# PLL.net
KiCad netlist of a schematic drawn in Altium Designer
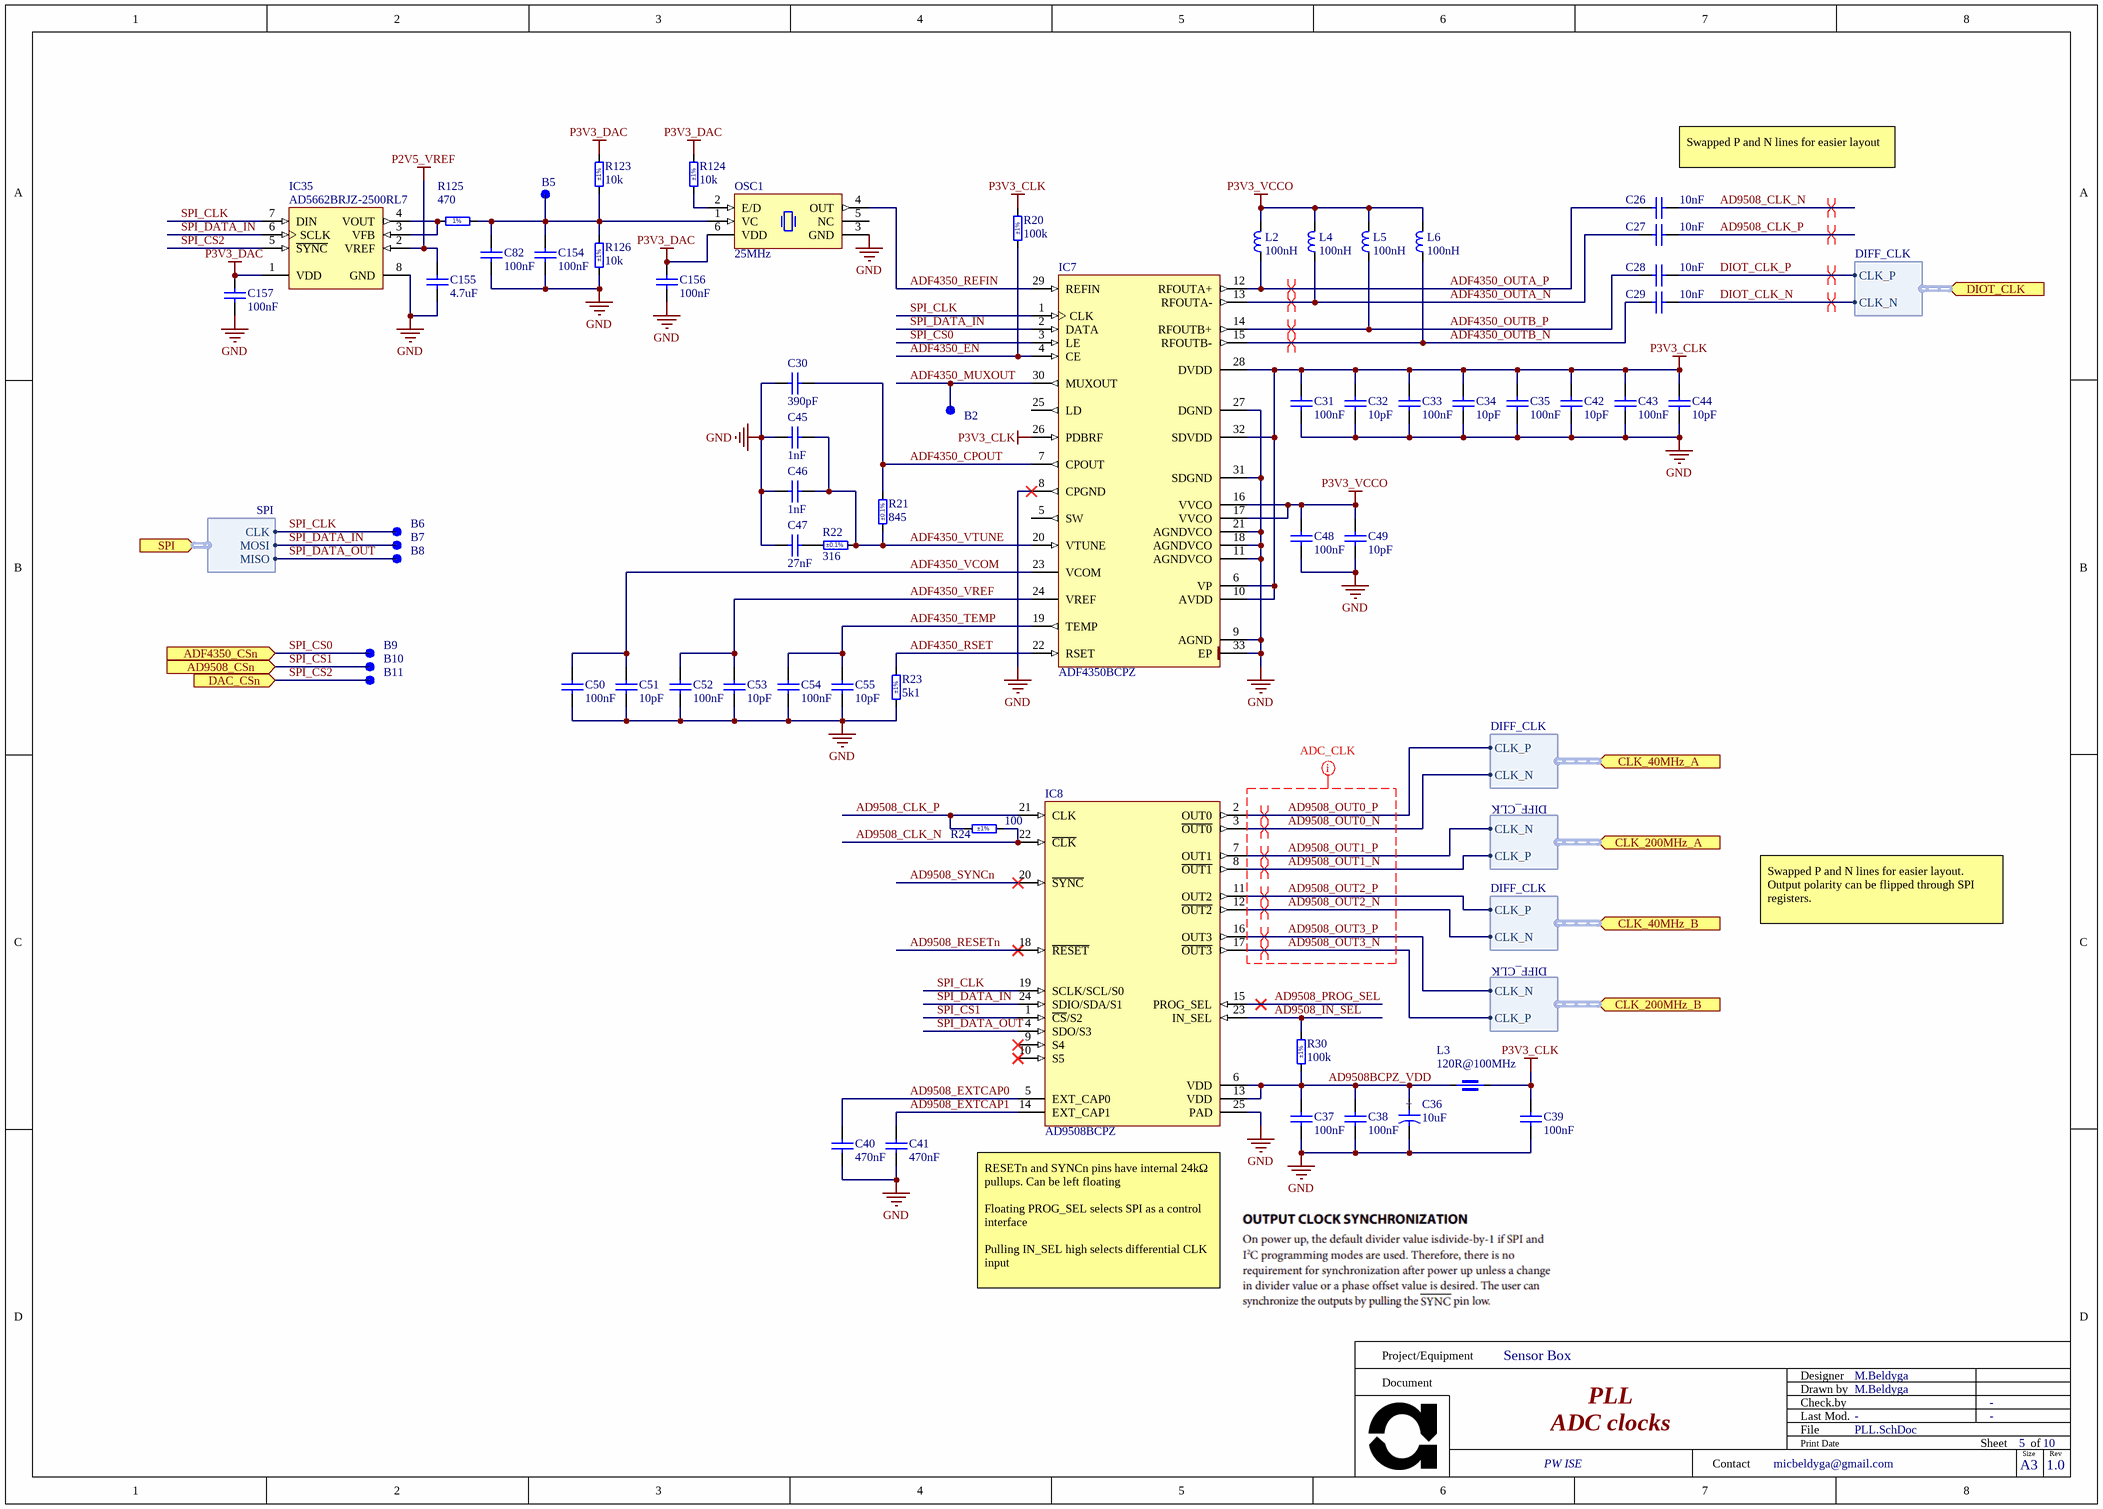
[diagram p0: PLL.SchDoc]

(export (version "E")
  (design (tool "Eeschema 10.0.6"))
  (components
    (comp (ref "B2")
      (value "SMD Pad")
      (footprint "C100")
      (description "Pad")
      (fields (field (name "PART NUMBER") "SMD_PAD_D1MM") (field (name "AUTHOR") "CERN DEM JLC"))
      (libsource (lib "Eletro-mechanical") (part "Single SMD Pad (Round)"))
    )
    (comp (ref "B5")
      (value "SMD Pad")
      (footprint "C100")
      (description "Pad")
      (fields (field (name "PART NUMBER") "SMD_PAD_D1MM") (field (name "AUTHOR") "CERN DEM JLC"))
      (libsource (lib "Eletro-mechanical") (part "Single SMD Pad (Round)"))
    )
    (comp (ref "B6")
      (value "SMD Pad")
      (footprint "C100")
      (description "Pad")
      (fields (field (name "PART NUMBER") "SMD_PAD_D1MM") (field (name "AUTHOR") "CERN DEM JLC"))
      (libsource (lib "Eletro-mechanical") (part "Single SMD Pad (Round)"))
    )
    (comp (ref "B7")
      (value "SMD Pad")
      (footprint "C100")
      (description "Pad")
      (fields (field (name "PART NUMBER") "SMD_PAD_D1MM") (field (name "AUTHOR") "CERN DEM JLC"))
      (libsource (lib "Eletro-mechanical") (part "Single SMD Pad (Round)"))
    )
    (comp (ref "B8")
      (value "SMD Pad")
      (footprint "C100")
      (description "Pad")
      (fields (field (name "PART NUMBER") "SMD_PAD_D1MM") (field (name "AUTHOR") "CERN DEM JLC"))
      (libsource (lib "Eletro-mechanical") (part "Single SMD Pad (Round)"))
    )
    (comp (ref "B9")
      (value "SMD Pad")
      (footprint "C100")
      (description "Pad")
      (fields (field (name "PART NUMBER") "SMD_PAD_D1MM") (field (name "AUTHOR") "CERN DEM JLC"))
      (libsource (lib "Eletro-mechanical") (part "Single SMD Pad (Round)"))
    )
    (comp (ref "B10")
      (value "SMD Pad")
      (footprint "C100")
      (description "Pad")
      (fields (field (name "PART NUMBER") "SMD_PAD_D1MM") (field (name "AUTHOR") "CERN DEM JLC"))
      (libsource (lib "Eletro-mechanical") (part "Single SMD Pad (Round)"))
    )
    (comp (ref "B11")
      (value "SMD Pad")
      (footprint "C100")
      (description "Pad")
      (fields (field (name "PART NUMBER") "SMD_PAD_D1MM") (field (name "AUTHOR") "CERN DEM JLC"))
      (libsource (lib "Eletro-mechanical") (part "Single SMD Pad (Round)"))
    )
    (comp (ref "C26")
      (value "10nF")
      (footprint "CAPC1005X55N")
      (description "Non-polarised capacitor")
      (fields
        (field (name "PART NUMBER") "CC0402_10NF_16V_10%_X7R")
        (field (name "VOLTAGE") "16V")
        (field (name "AUTHOR") "CERN DEM JLC")
      )
      (libsource (lib "Capacitors") (part "Capacitor - non polarized"))
    )
    (comp (ref "C27")
      (value "10nF")
      (footprint "CAPC1005X55N")
      (description "Non-polarised capacitor")
      (fields
        (field (name "PART NUMBER") "CC0402_10NF_16V_10%_X7R")
        (field (name "VOLTAGE") "16V")
        (field (name "AUTHOR") "CERN DEM JLC")
      )
      (libsource (lib "Capacitors") (part "Capacitor - non polarized"))
    )
    (comp (ref "C28")
      (value "10nF")
      (footprint "CAPC1005X55N")
      (description "Non-polarised capacitor")
      (fields
        (field (name "PART NUMBER") "CC0402_10NF_16V_10%_X7R")
        (field (name "VOLTAGE") "16V")
        (field (name "AUTHOR") "CERN DEM JLC")
      )
      (libsource (lib "Capacitors") (part "Capacitor - non polarized"))
    )
    (comp (ref "C29")
      (value "10nF")
      (footprint "CAPC1005X55N")
      (description "Non-polarised capacitor")
      (fields
        (field (name "PART NUMBER") "CC0402_10NF_16V_10%_X7R")
        (field (name "VOLTAGE") "16V")
        (field (name "AUTHOR") "CERN DEM JLC")
      )
      (libsource (lib "Capacitors") (part "Capacitor - non polarized"))
    )
    (comp (ref "C30")
      (value "390pF")
      (footprint "CAPC1005X55N")
      (description "Non-polarised capacitor")
      (fields
        (field (name "PART NUMBER") "CC0402_390PF_50V_1%_C0G_MURATA_GCM1555C1H391FA16")
        (field (name "VOLTAGE") "50V")
        (field (name "AUTHOR") "CERN DEM BC")
      )
      (libsource (lib "Capacitors") (part "Capacitor - non polarized"))
    )
    (comp (ref "C31")
      (value "100nF")
      (footprint "CAPC1005X55N")
      (description "Non-polarised capacitor")
      (fields
        (field (name "PART NUMBER") "CC0402_100NF_50V_10%_X7R")
        (field (name "VOLTAGE") "50V")
        (field (name "AUTHOR") "CERN DEM MR")
      )
      (libsource (lib "Capacitors") (part "Capacitor - non polarized"))
    )
    (comp (ref "C32")
      (value "10pF")
      (footprint "CAPC1005X55N")
      (description "Non-polarised capacitor")
      (fields
        (field (name "PART NUMBER") "CC0402_10PF_50V_5%_C0G")
        (field (name "VOLTAGE") "50V")
        (field (name "AUTHOR") "CERN DEM JLC")
      )
      (libsource (lib "Capacitors") (part "Capacitor - non polarized"))
    )
    (comp (ref "C33")
      (value "100nF")
      (footprint "CAPC1005X55N")
      (description "Non-polarised capacitor")
      (fields
        (field (name "PART NUMBER") "CC0402_100NF_50V_10%_X7R")
        (field (name "VOLTAGE") "50V")
        (field (name "AUTHOR") "CERN DEM MR")
      )
      (libsource (lib "Capacitors") (part "Capacitor - non polarized"))
    )
    (comp (ref "C34")
      (value "10pF")
      (footprint "CAPC1005X55N")
      (description "Non-polarised capacitor")
      (fields
        (field (name "PART NUMBER") "CC0402_10PF_50V_5%_C0G")
        (field (name "VOLTAGE") "50V")
        (field (name "AUTHOR") "CERN DEM JLC")
      )
      (libsource (lib "Capacitors") (part "Capacitor - non polarized"))
    )
    (comp (ref "C35")
      (value "100nF")
      (footprint "CAPC1005X55N")
      (description "Non-polarised capacitor")
      (fields
        (field (name "PART NUMBER") "CC0402_100NF_50V_10%_X7R")
        (field (name "VOLTAGE") "50V")
        (field (name "AUTHOR") "CERN DEM MR")
      )
      (libsource (lib "Capacitors") (part "Capacitor - non polarized"))
    )
    (comp (ref "C36")
      (value "10uF")
      (footprint "CAPMP3216X180N")
      (description "Polarised capacitor")
      (fields
        (field (name "PART NUMBER") "CTE3216-18_10UF_16V_20%_AVX_TCJ")
        (field (name "VOLTAGE") "16V")
        (field (name "AUTHOR") "CERN DEM JLC")
      )
      (libsource (lib "Capacitors") (part "Capacitor - polarized"))
    )
    (comp (ref "C37")
      (value "100nF")
      (footprint "CAPC1005X55N")
      (description "Non-polarised capacitor")
      (fields
        (field (name "PART NUMBER") "CC0402_100NF_50V_10%_X7R")
        (field (name "VOLTAGE") "50V")
        (field (name "AUTHOR") "CERN DEM MR")
      )
      (libsource (lib "Capacitors") (part "Capacitor - non polarized"))
    )
    (comp (ref "C38")
      (value "100nF")
      (footprint "CAPC1005X55N")
      (description "Non-polarised capacitor")
      (fields
        (field (name "PART NUMBER") "CC0402_100NF_50V_10%_X7R")
        (field (name "VOLTAGE") "50V")
        (field (name "AUTHOR") "CERN DEM MR")
      )
      (libsource (lib "Capacitors") (part "Capacitor - non polarized"))
    )
    (comp (ref "C39")
      (value "100nF")
      (footprint "CAPC1005X55N")
      (description "Non-polarised capacitor")
      (fields
        (field (name "PART NUMBER") "CC0402_100NF_50V_10%_X7R")
        (field (name "VOLTAGE") "50V")
        (field (name "AUTHOR") "CERN DEM MR")
      )
      (libsource (lib "Capacitors") (part "Capacitor - non polarized"))
    )
    (comp (ref "C40")
      (value "470nF")
      (footprint "CAPC1005X55N")
      (description "Non-polarised capacitor")
      (fields
        (field (name "PART NUMBER") "CC0402_470NF_16V_10%_X5R")
        (field (name "VOLTAGE") "16V")
        (field (name "AUTHOR") "CERN DEM JLC")
      )
      (libsource (lib "Capacitors") (part "Capacitor - non polarized"))
    )
    (comp (ref "C41")
      (value "470nF")
      (footprint "CAPC1005X55N")
      (description "Non-polarised capacitor")
      (fields
        (field (name "PART NUMBER") "CC0402_470NF_16V_10%_X5R")
        (field (name "VOLTAGE") "16V")
        (field (name "AUTHOR") "CERN DEM JLC")
      )
      (libsource (lib "Capacitors") (part "Capacitor - non polarized"))
    )
    (comp (ref "C42")
      (value "10pF")
      (footprint "CAPC1005X55N")
      (description "Non-polarised capacitor")
      (fields
        (field (name "PART NUMBER") "CC0402_10PF_50V_5%_C0G")
        (field (name "VOLTAGE") "50V")
        (field (name "AUTHOR") "CERN DEM JLC")
      )
      (libsource (lib "Capacitors") (part "Capacitor - non polarized"))
    )
    (comp (ref "C43")
      (value "100nF")
      (footprint "CAPC1005X55N")
      (description "Non-polarised capacitor")
      (fields
        (field (name "PART NUMBER") "CC0402_100NF_50V_10%_X7R")
        (field (name "VOLTAGE") "50V")
        (field (name "AUTHOR") "CERN DEM MR")
      )
      (libsource (lib "Capacitors") (part "Capacitor - non polarized"))
    )
    (comp (ref "C44")
      (value "10pF")
      (footprint "CAPC1005X55N")
      (description "Non-polarised capacitor")
      (fields
        (field (name "PART NUMBER") "CC0402_10PF_50V_5%_C0G")
        (field (name "VOLTAGE") "50V")
        (field (name "AUTHOR") "CERN DEM JLC")
      )
      (libsource (lib "Capacitors") (part "Capacitor - non polarized"))
    )
    (comp (ref "C45")
      (value "1nF")
      (footprint "CAPC1608X90N")
      (description "Non-polarised capacitor")
      (fields
        (field (name "PART NUMBER") "CC0603_1NF_50V_1%_NP0")
        (field (name "VOLTAGE") "50V")
        (field (name "AUTHOR") "CERN DEM JLC")
      )
      (libsource (lib "Capacitors") (part "Capacitor - non polarized"))
    )
    (comp (ref "C46")
      (value "1nF")
      (footprint "CAPC1608X90N")
      (description "Non-polarised capacitor")
      (fields
        (field (name "PART NUMBER") "CC0603_1NF_50V_1%_NP0")
        (field (name "VOLTAGE") "50V")
        (field (name "AUTHOR") "CERN DEM JLC")
      )
      (libsource (lib "Capacitors") (part "Capacitor - non polarized"))
    )
    (comp (ref "C47")
      (value "27nF")
      (footprint "CAPC1005X55N")
      (description "Non-polarised capacitor")
      (fields
        (field (name "PART NUMBER") "CC0402_27NF_25V_10%_X7R")
        (field (name "VOLTAGE") "25V")
        (field (name "AUTHOR") "CERN DEM JLC")
      )
      (libsource (lib "Capacitors") (part "Capacitor - non polarized"))
    )
    (comp (ref "C48")
      (value "100nF")
      (footprint "CAPC1005X55N")
      (description "Non-polarised capacitor")
      (fields
        (field (name "PART NUMBER") "CC0402_100NF_50V_10%_X7R")
        (field (name "VOLTAGE") "50V")
        (field (name "AUTHOR") "CERN DEM MR")
      )
      (libsource (lib "Capacitors") (part "Capacitor - non polarized"))
    )
    (comp (ref "C49")
      (value "10pF")
      (footprint "CAPC1005X55N")
      (description "Non-polarised capacitor")
      (fields
        (field (name "PART NUMBER") "CC0402_10PF_50V_5%_C0G")
        (field (name "VOLTAGE") "50V")
        (field (name "AUTHOR") "CERN DEM JLC")
      )
      (libsource (lib "Capacitors") (part "Capacitor - non polarized"))
    )
    (comp (ref "C50")
      (value "100nF")
      (footprint "CAPC1005X55N")
      (description "Non-polarised capacitor")
      (fields
        (field (name "PART NUMBER") "CC0402_100NF_50V_10%_X7R")
        (field (name "VOLTAGE") "50V")
        (field (name "AUTHOR") "CERN DEM MR")
      )
      (libsource (lib "Capacitors") (part "Capacitor - non polarized"))
    )
    (comp (ref "C51")
      (value "10pF")
      (footprint "CAPC1005X55N")
      (description "Non-polarised capacitor")
      (fields
        (field (name "PART NUMBER") "CC0402_10PF_50V_5%_C0G")
        (field (name "VOLTAGE") "50V")
        (field (name "AUTHOR") "CERN DEM JLC")
      )
      (libsource (lib "Capacitors") (part "Capacitor - non polarized"))
    )
    (comp (ref "C52")
      (value "100nF")
      (footprint "CAPC1005X55N")
      (description "Non-polarised capacitor")
      (fields
        (field (name "PART NUMBER") "CC0402_100NF_50V_10%_X7R")
        (field (name "VOLTAGE") "50V")
        (field (name "AUTHOR") "CERN DEM MR")
      )
      (libsource (lib "Capacitors") (part "Capacitor - non polarized"))
    )
    (comp (ref "C53")
      (value "10pF")
      (footprint "CAPC1005X55N")
      (description "Non-polarised capacitor")
      (fields
        (field (name "PART NUMBER") "CC0402_10PF_50V_5%_C0G")
        (field (name "VOLTAGE") "50V")
        (field (name "AUTHOR") "CERN DEM JLC")
      )
      (libsource (lib "Capacitors") (part "Capacitor - non polarized"))
    )
    (comp (ref "C54")
      (value "100nF")
      (footprint "CAPC1005X55N")
      (description "Non-polarised capacitor")
      (fields
        (field (name "PART NUMBER") "CC0402_100NF_50V_10%_X7R")
        (field (name "VOLTAGE") "50V")
        (field (name "AUTHOR") "CERN DEM MR")
      )
      (libsource (lib "Capacitors") (part "Capacitor - non polarized"))
    )
    (comp (ref "C55")
      (value "10pF")
      (footprint "CAPC1005X55N")
      (description "Non-polarised capacitor")
      (fields
        (field (name "PART NUMBER") "CC0402_10PF_50V_5%_C0G")
        (field (name "VOLTAGE") "50V")
        (field (name "AUTHOR") "CERN DEM JLC")
      )
      (libsource (lib "Capacitors") (part "Capacitor - non polarized"))
    )
    (comp (ref "C82")
      (value "100nF")
      (footprint "CAPC1005X55N")
      (description "Non-polarised capacitor")
      (fields
        (field (name "PART NUMBER") "CC0402_100NF_50V_10%_X7R")
        (field (name "VOLTAGE") "50V")
        (field (name "AUTHOR") "CERN DEM MR")
      )
      (libsource (lib "Capacitors") (part "Capacitor - non polarized"))
    )
    (comp (ref "C154")
      (value "100nF")
      (footprint "CAPC1005X55N")
      (description "Non-polarised capacitor")
      (fields
        (field (name "PART NUMBER") "CC0402_100NF_50V_10%_X7R")
        (field (name "VOLTAGE") "50V")
        (field (name "AUTHOR") "CERN DEM MR")
      )
      (libsource (lib "Capacitors") (part "Capacitor - non polarized"))
    )
    (comp (ref "C155")
      (value "4.7uF")
      (footprint "CAPC1608X90N")
      (description "Non-polarised capacitor")
      (fields
        (field (name "PART NUMBER") "CC0603_4.7UF_25V_10%_X5R")
        (field (name "VOLTAGE") "25V")
        (field (name "AUTHOR") "CERN DEM JLC")
      )
      (libsource (lib "Capacitors") (part "Capacitor - non polarized"))
    )
    (comp (ref "C156")
      (value "100nF")
      (footprint "CAPC1005X55N")
      (description "Non-polarised capacitor")
      (fields
        (field (name "PART NUMBER") "CC0402_100NF_50V_10%_X7R")
        (field (name "VOLTAGE") "50V")
        (field (name "AUTHOR") "CERN DEM MR")
      )
      (libsource (lib "Capacitors") (part "Capacitor - non polarized"))
    )
    (comp (ref "C157")
      (value "100nF")
      (footprint "CAPC1005X55N")
      (description "Non-polarised capacitor")
      (fields
        (field (name "PART NUMBER") "CC0402_100NF_50V_10%_X7R")
        (field (name "VOLTAGE") "50V")
        (field (name "AUTHOR") "CERN DEM MR")
      )
      (libsource (lib "Capacitors") (part "Capacitor - non polarized"))
    )
    (comp (ref "IC7")
      (value "ADF4350BCPZ")
      (footprint "QFN50P500X500X80-33N-S325")
      (description "Wideband Synthesizer with Integrated VCO")
      (fields
        (field (name "MANUFACTURER") "Analog Devices")
        (field (name "MANUFACTURER PART NUMBER") "ADF4351BCP")
        (field (name "AUTHOR") "Michal Beldyga")
      )
      (libsource (lib "Semiconductors") (part "ADF4350"))
    )
    (comp (ref "IC8")
      (value "AD9508BCPZ")
      (footprint "QFN50P400X400X80_HS-25N")
      (description "1.65 GHz Clock Fanout Buffer with Output Dividers and Delay Adjust")
      (fields (field (name "MANUFACTURER") "Analog Devices") (field (name "AUTHOR") "Michal Beldyga"))
      (libsource (lib "Semiconductors") (part "AD9508"))
    )
    (comp (ref "IC35")
      (value "AD5662BRJZ-2500RL7")
      (footprint "SOT65P280X145-8N")
      (description "2.7V to 5.5V, 250µA, Rail-to-Rail Output 16-Bit nanoDAC")
      (fields
        (field (name "MANUFACTURER") "ANALOG DEVICES")
        (field (name "MANUFACTURER PART NUMBER") "AD5662BRJZ-2")
        (field (name "AUTHOR") "CERN DEM JLC")
      )
      (libsource (lib "ICs And Semiconductors") (part "AD5662"))
    )
    (comp (ref "L2")
      (value "100nH")
      (footprint "INDC1005X55N")
      (description "Inductor")
      (fields
        (field (name "PART NUMBER") "IND0402_100NH_5%_JOHANSON_ L-07CR10JV6T")
        (field (name "TOLERANCE") "±5%")
        (field (name "AUTHOR") "Michal Beldyga")
      )
      (libsource (lib "Inductors Transformers") (part "Inductor"))
    )
    (comp (ref "L3")
      (value "120R@100MHz")
      (footprint "INDC1608X65N")
      (fields
        (field (name "PART NUMBER") "IND0603_MURATA_BLM18SG121TN1D")
        (field (name "POWER") "3A")
        (field (name "TOLERANCE") "±25%")
        (field (name "AUTHOR") "CERN DEM JLC")
      )
      (libsource (lib "Inductors & Transformers") (part "Ferrite Bead"))
    )
    (comp (ref "L4")
      (value "100nH")
      (footprint "INDC1005X55N")
      (description "Inductor")
      (fields
        (field (name "PART NUMBER") "IND0402_100NH_5%_JOHANSON_ L-07CR10JV6T")
        (field (name "TOLERANCE") "±5%")
        (field (name "AUTHOR") "Michal Beldyga")
      )
      (libsource (lib "Inductors Transformers") (part "Inductor"))
    )
    (comp (ref "L5")
      (value "100nH")
      (footprint "INDC1005X55N")
      (description "Inductor")
      (fields
        (field (name "PART NUMBER") "IND0402_100NH_5%_JOHANSON_ L-07CR10JV6T")
        (field (name "TOLERANCE") "±5%")
        (field (name "AUTHOR") "Michal Beldyga")
      )
      (libsource (lib "Inductors Transformers") (part "Inductor"))
    )
    (comp (ref "L6")
      (value "100nH")
      (footprint "INDC1005X55N")
      (description "Inductor")
      (fields
        (field (name "PART NUMBER") "IND0402_100NH_5%_JOHANSON_ L-07CR10JV6T")
        (field (name "TOLERANCE") "±5%")
        (field (name "AUTHOR") "Michal Beldyga")
      )
      (libsource (lib "Inductors Transformers") (part "Inductor"))
    )
    (comp (ref "OSC1")
      (value "25MHz")
      (footprint "OSC_PERICOM_FRETHE025")
      (description "3.3V CMOS 25.000MHz Ethernet VCXO")
      (fields
        (field (name "PART NUMBER") "OSC_25MHZ_PERICOM_FRETHE025")
        (field (name "MANUFACTURER") "PERICOM")
        (field (name "AUTHOR") "CERN DEM JLC")
      )
      (libsource (lib "ICs And Semiconductors") (part "Oscillator PERICOM_FRETHE025"))
    )
    (comp (ref "R20")
      (value "100k")
      (footprint "RESC1005X40N")
      (description "Resistor - 1%")
      (fields
        (field (name "TOLERANCE") "±1%")
        (field (name "PART NUMBER") "R0402_100K_1%_0.0625W_100PPM")
        (field (name "POWER") "0.0625W")
        (field (name "AUTHOR") "CERN DEM JLC")
      )
      (libsource (lib "Resistors") (part "Resistor - 1%"))
    )
    (comp (ref "R21")
      (value "845")
      (footprint "RESC1608X55N")
      (description "Resistor - 0.1%")
      (fields
        (field (name "TOLERANCE") "±0.1%")
        (field (name "PART NUMBER") "R0603_845R_0.1%_0.063W_10PPM")
        (field (name "POWER") "0.063W")
        (field (name "AUTHOR") "CERN DEM JLC")
      )
      (libsource (lib "Resistors") (part "Resistor - 0.1%"))
    )
    (comp (ref "R22")
      (value "316")
      (footprint "RESC1608X55N")
      (description "Resistor - 0.1%")
      (fields
        (field (name "TOLERANCE") "±0.1%")
        (field (name "PART NUMBER") "R0603_316R_0.1%_0.063W_10PPM")
        (field (name "POWER") "0.063W")
        (field (name "AUTHOR") "CERN DEM JLC")
      )
      (libsource (lib "Resistors") (part "Resistor - 0.1%"))
    )
    (comp (ref "R23")
      (value "5k1")
      (footprint "RESC1005X40N")
      (description "Resistor - 1%")
      (fields
        (field (name "TOLERANCE") "±1%")
        (field (name "PART NUMBER") "R0402_5K1_1%_0.0625W_100PPM")
        (field (name "POWER") "0.0625W")
        (field (name "AUTHOR") "CERN DEM JLC")
      )
      (libsource (lib "Resistors") (part "Resistor - 1%"))
    )
    (comp (ref "R24")
      (value "100")
      (footprint "RESC1005X40N")
      (description "Resistor - 1%")
      (fields
        (field (name "TOLERANCE") "±1%")
        (field (name "PART NUMBER") "R0402_100R_1%_0.1W_100PPM")
        (field (name "POWER") "0.1W")
        (field (name "AUTHOR") "CERN DEM JLC")
      )
      (libsource (lib "Resistors") (part "Resistor - 1%"))
    )
    (comp (ref "R30")
      (value "100k")
      (footprint "RESC1005X40N")
      (description "Resistor - 1%")
      (fields
        (field (name "TOLERANCE") "±1%")
        (field (name "PART NUMBER") "R0402_100K_1%_0.0625W_100PPM")
        (field (name "POWER") "0.0625W")
        (field (name "AUTHOR") "CERN DEM JLC")
      )
      (libsource (lib "Resistors") (part "Resistor - 1%"))
    )
    (comp (ref "R123")
      (value "10k")
      (footprint "RESC1005X40N")
      (description "Resistor - 1%")
      (fields
        (field (name "TOLERANCE") "±1%")
        (field (name "PART NUMBER") "R0402_10K_1%_0.0625W_100PPM")
        (field (name "POWER") "0.0625W")
        (field (name "AUTHOR") "CERN DEM JLC")
      )
      (libsource (lib "Resistors") (part "Resistor - 1%"))
    )
    (comp (ref "R124")
      (value "10k")
      (footprint "RESC1005X40N")
      (description "Resistor - 1%")
      (fields
        (field (name "TOLERANCE") "±1%")
        (field (name "PART NUMBER") "R0402_10K_1%_0.0625W_100PPM")
        (field (name "POWER") "0.0625W")
        (field (name "AUTHOR") "CERN DEM JLC")
      )
      (libsource (lib "Resistors") (part "Resistor - 1%"))
    )
    (comp (ref "R125")
      (value "470")
      (footprint "RESC1005X40N")
      (description "Resistor - 1%")
      (fields
        (field (name "PART NUMBER") "R0402_470R_1%_0.0625W_100PPM")
        (field (name "POWER") "0.0625W")
        (field (name "AUTHOR") "CERN DEM JLC")
      )
      (libsource (lib "Resistors") (part "Resistor - 1%"))
    )
    (comp (ref "R126")
      (value "10k")
      (footprint "RESC1005X40N")
      (description "Resistor - 1%")
      (fields
        (field (name "TOLERANCE") "±1%")
        (field (name "PART NUMBER") "R0402_10K_1%_0.0625W_100PPM")
        (field (name "POWER") "0.0625W")
        (field (name "AUTHOR") "CERN DEM JLC")
      )
      (libsource (lib "Resistors") (part "Resistor - 1%"))
    )
  )
  (nets
    (net (code "3") (name "/AD9508BCPZ_VDD") (class "Default")
      (node (ref "C36") (pin "1") (pinfunction "1_1") (pintype "passive"))
      (node (ref "C37") (pin "2") (pinfunction "2_2") (pintype "passive"))
      (node (ref "C38") (pin "2") (pinfunction "2_2") (pintype "passive"))
      (node (ref "IC8") (pin "13") (pinfunction "VDD_13") (pintype "power_in"))
      (node (ref "IC8") (pin "6") (pinfunction "VDD_6") (pintype "power_in"))
      (node (ref "L3") (pin "2") (pinfunction "2_2") (pintype "passive"))
      (node (ref "R30") (pin "1") (pinfunction "1_1") (pintype "passive"))
    )
    (net (code "4") (name "/AD9508_CLK_N") (class "Default")
      (node (ref "C26") (pin "1") (pinfunction "1_1") (pintype "passive"))
      (node (ref "IC8") (pin "22") (pinfunction "~{CLK}_22") (pintype "input"))
      (node (ref "R24") (pin "2") (pinfunction "2_2") (pintype "passive"))
    )
    (net (code "5") (name "/AD9508_CLK_P") (class "Default")
      (node (ref "C27") (pin "1") (pinfunction "1_1") (pintype "passive"))
      (node (ref "IC8") (pin "21") (pinfunction "CLK_21") (pintype "input"))
      (node (ref "R24") (pin "1") (pinfunction "1_1") (pintype "passive"))
    )
    (net (code "6") (name "/AD9508_EXTCAP0") (class "Default")
      (node (ref "C40") (pin "2") (pinfunction "2_2") (pintype "passive"))
      (node (ref "IC8") (pin "5") (pinfunction "EXT_CAP0_5") (pintype "power_in"))
    )
    (net (code "7") (name "/AD9508_EXTCAP1") (class "Default")
      (node (ref "C41") (pin "2") (pinfunction "2_2") (pintype "passive"))
      (node (ref "IC8") (pin "14") (pinfunction "EXT_CAP1_14") (pintype "power_in"))
    )
    (net (code "8") (name "/AD9508_IN_SEL") (class "Default")
      (node (ref "IC8") (pin "23") (pinfunction "IN_SEL_23") (pintype "input"))
      (node (ref "R30") (pin "2") (pinfunction "2_2") (pintype "passive"))
    )
    (net (code "9") (name "/AD9508_OUT0_N") (class "Default")
      (node (ref "IC8") (pin "3") (pinfunction "~{OUT0}_3") (pintype "output"))
    )
    (net (code "10") (name "/AD9508_OUT0_P") (class "Default")
      (node (ref "IC8") (pin "2") (pinfunction "OUT0_2") (pintype "output"))
    )
    (net (code "11") (name "/AD9508_OUT1_N") (class "Default")
      (node (ref "IC8") (pin "8") (pinfunction "~{OUT1}_8") (pintype "output"))
    )
    (net (code "12") (name "/AD9508_OUT1_P") (class "Default")
      (node (ref "IC8") (pin "7") (pinfunction "OUT1_7") (pintype "output"))
    )
    (net (code "13") (name "/AD9508_OUT2_N") (class "Default")
      (node (ref "IC8") (pin "12") (pinfunction "~{OUT2}_12") (pintype "output"))
    )
    (net (code "14") (name "/AD9508_OUT2_P") (class "Default")
      (node (ref "IC8") (pin "11") (pinfunction "OUT2_11") (pintype "output"))
    )
    (net (code "15") (name "/AD9508_OUT3_N") (class "Default")
      (node (ref "IC8") (pin "17") (pinfunction "~{OUT3}_17") (pintype "output"))
    )
    (net (code "16") (name "/AD9508_OUT3_P") (class "Default")
      (node (ref "IC8") (pin "16") (pinfunction "OUT3_16") (pintype "output"))
    )
    (net (code "17") (name "/AD9508_PROG_SEL") (class "Default")
      (node (ref "IC8") (pin "15") (pinfunction "PROG_SEL_15") (pintype "input"))
    )
    (net (code "18") (name "/AD9508_RESETn") (class "Default")
      (node (ref "IC8") (pin "18") (pinfunction "~{RESET}_18") (pintype "input+no_connect"))
    )
    (net (code "19") (name "/AD9508_SYNCn") (class "Default")
      (node (ref "IC8") (pin "20") (pinfunction "~{SYNC}_20") (pintype "input+no_connect"))
    )
    (net (code "20") (name "/ADF4350_CPOUT") (class "Default")
      (node (ref "C30") (pin "2") (pinfunction "2_2") (pintype "passive"))
      (node (ref "IC7") (pin "7") (pinfunction "CPOUT_7") (pintype "output"))
      (node (ref "R21") (pin "1") (pinfunction "1_1") (pintype "passive"))
    )
    (net (code "21") (name "/ADF4350_EN") (class "Default")
      (node (ref "IC7") (pin "4") (pinfunction "CE_4") (pintype "input"))
      (node (ref "R20") (pin "1") (pinfunction "1_1") (pintype "passive"))
    )
    (net (code "22") (name "/ADF4350_MUXOUT") (class "Default")
      (node (ref "B2") (pin "1") (pinfunction "1_1") (pintype "bidirectional"))
      (node (ref "IC7") (pin "30") (pinfunction "MUXOUT_30") (pintype "output"))
    )
    (net (code "23") (name "/ADF4350_OUTA_N") (class "Default")
      (node (ref "C27") (pin "2") (pinfunction "2_2") (pintype "passive"))
      (node (ref "IC7") (pin "13") (pinfunction "RFOUTA-_13") (pintype "output"))
      (node (ref "L4") (pin "1") (pinfunction "1_1") (pintype "passive"))
    )
    (net (code "24") (name "/ADF4350_OUTA_P") (class "Default")
      (node (ref "C26") (pin "2") (pinfunction "2_2") (pintype "passive"))
      (node (ref "IC7") (pin "12") (pinfunction "RFOUTA+_12") (pintype "output"))
      (node (ref "L2") (pin "1") (pinfunction "1_1") (pintype "passive"))
    )
    (net (code "25") (name "/ADF4350_OUTB_N") (class "Default")
      (node (ref "C29") (pin "2") (pinfunction "2_2") (pintype "passive"))
      (node (ref "IC7") (pin "15") (pinfunction "RFOUTB-_15") (pintype "output"))
      (node (ref "L6") (pin "1") (pinfunction "1_1") (pintype "passive"))
    )
    (net (code "26") (name "/ADF4350_OUTB_P") (class "Default")
      (node (ref "C28") (pin "2") (pinfunction "2_2") (pintype "passive"))
      (node (ref "IC7") (pin "14") (pinfunction "RFOUTB+_14") (pintype "output"))
      (node (ref "L5") (pin "1") (pinfunction "1_1") (pintype "passive"))
    )
    (net (code "27") (name "/ADF4350_REFIN") (class "Default")
      (node (ref "IC7") (pin "29") (pinfunction "REFIN_29") (pintype "input"))
      (node (ref "OSC1") (pin "4") (pinfunction "OUT_4") (pintype "output"))
    )
    (net (code "28") (name "/ADF4350_RSET") (class "Default")
      (node (ref "IC7") (pin "22") (pinfunction "RSET_22") (pintype "input"))
      (node (ref "R23") (pin "2") (pinfunction "2_2") (pintype "passive"))
    )
    (net (code "29") (name "/ADF4350_TEMP") (class "Default")
      (node (ref "C54") (pin "2") (pinfunction "2_2") (pintype "passive"))
      (node (ref "C55") (pin "2") (pinfunction "2_2") (pintype "passive"))
      (node (ref "IC7") (pin "19") (pinfunction "TEMP_19") (pintype "output"))
    )
    (net (code "30") (name "/ADF4350_VCOM") (class "Default")
      (node (ref "C50") (pin "2") (pinfunction "2_2") (pintype "passive"))
      (node (ref "C51") (pin "2") (pinfunction "2_2") (pintype "passive"))
      (node (ref "IC7") (pin "23") (pinfunction "VCOM_23") (pintype "passive"))
    )
    (net (code "31") (name "/ADF4350_VREF") (class "Default")
      (node (ref "C52") (pin "2") (pinfunction "2_2") (pintype "passive"))
      (node (ref "C53") (pin "2") (pinfunction "2_2") (pintype "passive"))
      (node (ref "IC7") (pin "24") (pinfunction "VREF_24") (pintype "passive"))
    )
    (net (code "32") (name "/ADF4350_VTUNE") (class "Default")
      (node (ref "C45") (pin "2") (pinfunction "2_2") (pintype "passive"))
      (node (ref "C46") (pin "2") (pinfunction "2_2") (pintype "passive"))
      (node (ref "IC7") (pin "20") (pinfunction "VTUNE_20") (pintype "input"))
      (node (ref "R21") (pin "2") (pinfunction "2_2") (pintype "passive"))
      (node (ref "R22") (pin "2") (pinfunction "2_2") (pintype "passive"))
    )
    (net (code "33") (name "/DIOT_CLK_N") (class "Default")
      (node (ref "C29") (pin "1") (pinfunction "1_1") (pintype "passive"))
    )
    (net (code "34") (name "/DIOT_CLK_P") (class "Default")
      (node (ref "C28") (pin "1") (pinfunction "1_1") (pintype "passive"))
    )
    (net (code "35") (name "/SPI_CLK") (class "Default")
      (node (ref "B6") (pin "1") (pinfunction "1_1") (pintype "bidirectional"))
      (node (ref "IC35") (pin "7") (pinfunction "DIN_7") (pintype "input"))
      (node (ref "IC7") (pin "1") (pinfunction "CLK_1") (pintype "input"))
      (node (ref "IC8") (pin "19") (pinfunction "SCLK/SCL/S0_19") (pintype "input"))
    )
    (net (code "36") (name "/SPI_CS0") (class "Default")
      (node (ref "B9") (pin "1") (pinfunction "1_1") (pintype "bidirectional"))
      (node (ref "IC7") (pin "3") (pinfunction "LE_3") (pintype "input"))
    )
    (net (code "37") (name "/SPI_CS1") (class "Default")
      (node (ref "B10") (pin "1") (pinfunction "1_1") (pintype "bidirectional"))
      (node (ref "IC8") (pin "1") (pinfunction "~{CS}/S2_1") (pintype "input"))
    )
    (net (code "38") (name "/SPI_CS2") (class "Default")
      (node (ref "B11") (pin "1") (pinfunction "1_1") (pintype "bidirectional"))
      (node (ref "IC35") (pin "5") (pinfunction "~{SYNC}_5") (pintype "input"))
    )
    (net (code "39") (name "/SPI_DATA_IN") (class "Default")
      (node (ref "B7") (pin "1") (pinfunction "1_1") (pintype "bidirectional"))
      (node (ref "IC35") (pin "6") (pinfunction "SCLK_6") (pintype "input"))
      (node (ref "IC7") (pin "2") (pinfunction "DATA_2") (pintype "input"))
      (node (ref "IC8") (pin "24") (pinfunction "SDIO/SDA/S1_24") (pintype "input"))
    )
    (net (code "40") (name "/SPI_DATA_OUT") (class "Default")
      (node (ref "B8") (pin "1") (pinfunction "1_1") (pintype "bidirectional"))
      (node (ref "IC8") (pin "4") (pinfunction "SDO/S3_4") (pintype "input"))
    )
    (net (code "43") (name "GND") (class "Default")
      (node (ref "C154") (pin "1") (pinfunction "1_1") (pintype "passive"))
      (node (ref "C155") (pin "1") (pinfunction "1_1") (pintype "passive"))
      (node (ref "C156") (pin "1") (pinfunction "1_1") (pintype "passive"))
      (node (ref "C157") (pin "1") (pinfunction "1_1") (pintype "passive"))
      (node (ref "C30") (pin "1") (pinfunction "1_1") (pintype "passive"))
      (node (ref "C31") (pin "1") (pinfunction "1_1") (pintype "passive"))
      (node (ref "C32") (pin "1") (pinfunction "1_1") (pintype "passive"))
      (node (ref "C33") (pin "1") (pinfunction "1_1") (pintype "passive"))
      (node (ref "C34") (pin "1") (pinfunction "1_1") (pintype "passive"))
      (node (ref "C35") (pin "1") (pinfunction "1_1") (pintype "passive"))
      (node (ref "C36") (pin "2") (pinfunction "2_2") (pintype "passive"))
      (node (ref "C37") (pin "1") (pinfunction "1_1") (pintype "passive"))
      (node (ref "C38") (pin "1") (pinfunction "1_1") (pintype "passive"))
      (node (ref "C39") (pin "1") (pinfunction "1_1") (pintype "passive"))
      (node (ref "C40") (pin "1") (pinfunction "1_1") (pintype "passive"))
      (node (ref "C41") (pin "1") (pinfunction "1_1") (pintype "passive"))
      (node (ref "C42") (pin "1") (pinfunction "1_1") (pintype "passive"))
      (node (ref "C43") (pin "1") (pinfunction "1_1") (pintype "passive"))
      (node (ref "C44") (pin "1") (pinfunction "1_1") (pintype "passive"))
      (node (ref "C45") (pin "1") (pinfunction "1_1") (pintype "passive"))
      (node (ref "C46") (pin "1") (pinfunction "1_1") (pintype "passive"))
      (node (ref "C47") (pin "1") (pinfunction "1_1") (pintype "passive"))
      (node (ref "C48") (pin "1") (pinfunction "1_1") (pintype "passive"))
      (node (ref "C49") (pin "1") (pinfunction "1_1") (pintype "passive"))
      (node (ref "C50") (pin "1") (pinfunction "1_1") (pintype "passive"))
      (node (ref "C51") (pin "1") (pinfunction "1_1") (pintype "passive"))
      (node (ref "C52") (pin "1") (pinfunction "1_1") (pintype "passive"))
      (node (ref "C53") (pin "1") (pinfunction "1_1") (pintype "passive"))
      (node (ref "C54") (pin "1") (pinfunction "1_1") (pintype "passive"))
      (node (ref "C55") (pin "1") (pinfunction "1_1") (pintype "passive"))
      (node (ref "C82") (pin "1") (pinfunction "1_1") (pintype "passive"))
      (node (ref "IC35") (pin "8") (pinfunction "GND_8") (pintype "power_in"))
      (node (ref "IC7") (pin "11") (pinfunction "AGNDVCO_11") (pintype "power_in"))
      (node (ref "IC7") (pin "18") (pinfunction "AGNDVCO_18") (pintype "power_in"))
      (node (ref "IC7") (pin "21") (pinfunction "AGNDVCO_21") (pintype "power_in"))
      (node (ref "IC7") (pin "27") (pinfunction "DGND_27") (pintype "power_in"))
      (node (ref "IC7") (pin "31") (pinfunction "SDGND_31") (pintype "power_in"))
      (node (ref "IC7") (pin "33") (pinfunction "EP_33") (pintype "power_in"))
      (node (ref "IC7") (pin "8") (pinfunction "CPGND_8") (pintype "output"))
      (node (ref "IC7") (pin "9") (pinfunction "AGND_9") (pintype "power_in"))
      (node (ref "IC8") (pin "25") (pinfunction "PAD_25") (pintype "power_in"))
      (node (ref "OSC1") (pin "3") (pinfunction "GND_3") (pintype "power_in"))
      (node (ref "R126") (pin "1") (pinfunction "1_1") (pintype "passive"))
      (node (ref "R23") (pin "1") (pinfunction "1_1") (pintype "passive"))
    )
    (net (code "44") (name "Net-(C47-Pad2)") (class "Default")
      (node (ref "C47") (pin "2") (pinfunction "2_2") (pintype "passive"))
      (node (ref "R22") (pin "1") (pinfunction "1_1") (pintype "passive"))
    )
    (net (code "45") (name "Net-(IC35-VFB)") (class "Default")
      (node (ref "IC35") (pin "3") (pinfunction "VFB_3") (pintype "input"))
      (node (ref "IC35") (pin "4") (pinfunction "VOUT_4") (pintype "output"))
      (node (ref "R125") (pin "1") (pinfunction "1_1") (pintype "passive"))
    )
    (net (code "46") (name "Net-(OSC1-E{slash}D)") (class "Default")
      (node (ref "OSC1") (pin "2") (pinfunction "E/D_2") (pintype "input"))
      (node (ref "R124") (pin "2") (pinfunction "2_2") (pintype "passive"))
    )
    (net (code "47") (name "Net-(OSC1-VC)") (class "Default")
      (node (ref "B5") (pin "1") (pinfunction "1_1") (pintype "bidirectional"))
      (node (ref "C154") (pin "2") (pinfunction "2_2") (pintype "passive"))
      (node (ref "C82") (pin "2") (pinfunction "2_2") (pintype "passive"))
      (node (ref "OSC1") (pin "1") (pinfunction "VC_1") (pintype "input"))
      (node (ref "R123") (pin "1") (pinfunction "1_1") (pintype "passive"))
      (node (ref "R125") (pin "2") (pinfunction "2_2") (pintype "passive"))
      (node (ref "R126") (pin "2") (pinfunction "2_2") (pintype "passive"))
    )
    (net (code "48") (name "P2V5_VREF") (class "Default")
      (node (ref "C155") (pin "2") (pinfunction "2_2") (pintype "passive"))
      (node (ref "IC35") (pin "2") (pinfunction "VREF_2") (pintype "input"))
    )
    (net (code "49") (name "P3V3_CLK") (class "Default")
      (node (ref "C31") (pin "2") (pinfunction "2_2") (pintype "passive"))
      (node (ref "C32") (pin "2") (pinfunction "2_2") (pintype "passive"))
      (node (ref "C33") (pin "2") (pinfunction "2_2") (pintype "passive"))
      (node (ref "C34") (pin "2") (pinfunction "2_2") (pintype "passive"))
      (node (ref "C35") (pin "2") (pinfunction "2_2") (pintype "passive"))
      (node (ref "C39") (pin "2") (pinfunction "2_2") (pintype "passive"))
      (node (ref "C42") (pin "2") (pinfunction "2_2") (pintype "passive"))
      (node (ref "C43") (pin "2") (pinfunction "2_2") (pintype "passive"))
      (node (ref "C44") (pin "2") (pinfunction "2_2") (pintype "passive"))
      (node (ref "IC7") (pin "10") (pinfunction "AVDD_10") (pintype "power_in"))
      (node (ref "IC7") (pin "26") (pinfunction "PDBRF_26") (pintype "input"))
      (node (ref "IC7") (pin "28") (pinfunction "DVDD_28") (pintype "power_in"))
      (node (ref "IC7") (pin "32") (pinfunction "SDVDD_32") (pintype "power_in"))
      (node (ref "IC7") (pin "6") (pinfunction "VP_6") (pintype "power_in"))
      (node (ref "L3") (pin "1") (pinfunction "1_1") (pintype "passive"))
      (node (ref "R20") (pin "2") (pinfunction "2_2") (pintype "passive"))
    )
    (net (code "50") (name "P3V3_DAC") (class "Default")
      (node (ref "C156") (pin "2") (pinfunction "2_2") (pintype "passive"))
      (node (ref "C157") (pin "2") (pinfunction "2_2") (pintype "passive"))
      (node (ref "IC35") (pin "1") (pinfunction "VDD_1") (pintype "power_in"))
      (node (ref "OSC1") (pin "6") (pinfunction "VDD_6") (pintype "power_in"))
      (node (ref "R123") (pin "2") (pinfunction "2_2") (pintype "passive"))
      (node (ref "R124") (pin "1") (pinfunction "1_1") (pintype "passive"))
    )
    (net (code "51") (name "P3V3_VCCO") (class "Default")
      (node (ref "C48") (pin "2") (pinfunction "2_2") (pintype "passive"))
      (node (ref "C49") (pin "2") (pinfunction "2_2") (pintype "passive"))
      (node (ref "IC7") (pin "16") (pinfunction "VVCO_16") (pintype "power_in"))
      (node (ref "IC7") (pin "17") (pinfunction "VVCO_17") (pintype "power_in"))
      (node (ref "L2") (pin "2") (pinfunction "2_2") (pintype "passive"))
      (node (ref "L4") (pin "2") (pinfunction "2_2") (pintype "passive"))
      (node (ref "L5") (pin "2") (pinfunction "2_2") (pintype "passive"))
      (node (ref "L6") (pin "2") (pinfunction "2_2") (pintype "passive"))
    )
    (net (code "52") (name "unconnected-(IC7-LD-Pad25)") (class "Default")
      (node (ref "IC7") (pin "25") (pinfunction "LD_25") (pintype "output"))
    )
    (net (code "53") (name "unconnected-(IC7-SW-Pad5)") (class "Default")
      (node (ref "IC7") (pin "5") (pinfunction "SW_5") (pintype "output"))
    )
    (net (code "54") (name "unconnected-(IC8-S4-Pad9)") (class "Default")
      (node (ref "IC8") (pin "9") (pinfunction "S4_9") (pintype "input+no_connect"))
    )
    (net (code "55") (name "unconnected-(IC8-S5-Pad10)") (class "Default")
      (node (ref "IC8") (pin "10") (pinfunction "S5_10") (pintype "input+no_connect"))
    )
    (net (code "56") (name "unconnected-(OSC1-NC-Pad5)") (class "Default")
      (node (ref "OSC1") (pin "5") (pinfunction "NC_5") (pintype "passive"))
    )
  )
)
